# Power_DDRTermination.net
KiCad netlist of a schematic drawn in Altium Designer
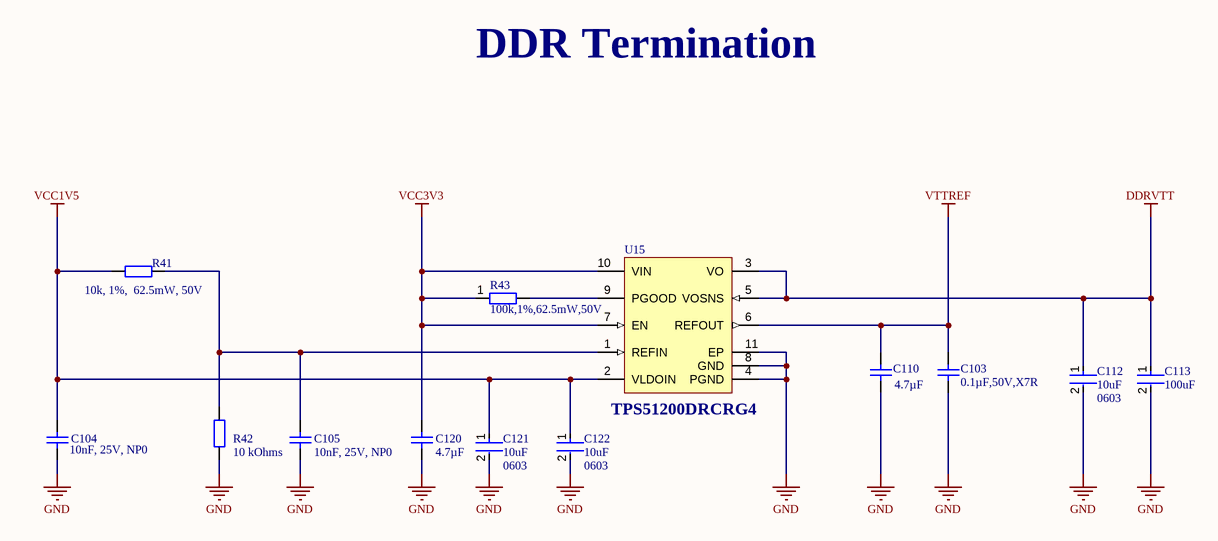
[diagram p0: Power_DDRTermination.SchDoc]

(export (version "E")
  (design (tool "Eeschema 10.0.6"))
  (components
    (comp (ref "C103")
      (value "0.1µF,50V,X7R")
      (footprint "CAP0402i")
      (description "0402, 0.1uF, 10%,  50V, X7R")
      (fields (field (name "PART NUMBER") "C1005X7R1H104K050BE") (field (name "VOLTAGE") "50V"))
      (libsource (lib "AmpherLib") (part "Cap_0.1uF_50V_X7R_0402"))
    )
    (comp (ref "C104")
      (value "10nF, 25V, NP0")
      (footprint "CAP0402i")
      (description "0402,10nF,5%,25V,NP0")
      (fields (field (name "PART NUMBER") "GRM1555C1E103JE01J") (field (name "MANUFACTURER") "Murata"))
      (libsource (lib "AmpherLib") (part "Cap_10nF_25V_NP0_0402"))
    )
    (comp (ref "C105")
      (value "10nF, 25V, NP0")
      (footprint "CAP0402i")
      (description "0402,10nF,5%,25V,NP0")
      (fields (field (name "PART NUMBER") "GRM1555C1E103JE01J") (field (name "MANUFACTURER") "Murata"))
      (libsource (lib "AmpherLib") (part "Cap_10nF_25V_NP0_0402"))
    )
    (comp (ref "C110")
      (value "4.7µF")
      (footprint "CAP0402i")
      (description "CAP CER 4.7UF 10V X5R 0402")
      (fields
        (field (name "TOLERANCE") "10%")
        (field (name "CAPACITANCE") "4.7µF")
        (field (name "PART NUMBER") "C1005X5R1A475K050BC")
      )
      (libsource (lib "AmpherLib") (part "Cap_4.7uF_10V_10%_0402"))
    )
    (comp (ref "C112")
      (value "GRM188R60J106ME47D")
      (footprint "FP-GRM188-0_1-e0_2_0_55-IPC_A")
      (description "Chip Multilayer Ceramic Capacitors for General Purpose, 0603, 10uF, X5R, 15%, 20%, 6.3V")
      (fields
        (field (name "CAPACITANCE") "10uF")
        (field (name "CASE/PACKAGE") "0603")
        (field (name "VOLTAGE") "6.3V")
        (field (name "TOLERANCE") "20%")
      )
      (libsource (lib "Altium Content Vault") (part "02cd4be3c70576c341d710602a673aa"))
    )
    (comp (ref "C113")
      (value "100uF")
      (footprint "FP-GRM32-0_3-MFG")
      (description "CAP CER 100UF 6.3V X5R 1210")
      (fields
        (field (name "OCTOPART") "https://octopart.com/grm32er60j107me20l-murata-197007")
        (field (name "3DS PART NUMBER") "220-00002")
      )
      (libsource (lib "Altium Content Vault") (part "11868f565c42a9108669ba33697ecf6"))
    )
    (comp (ref "C120")
      (value "4.7µF")
      (footprint "CAP0402i")
      (description "CAP CER 4.7UF 10V X5R 0402")
      (fields
        (field (name "TOLERANCE") "10%")
        (field (name "CAPACITANCE") "4.7µF")
        (field (name "PART NUMBER") "C1005X5R1A475K050BC")
      )
      (libsource (lib "AmpherLib") (part "Cap_4.7uF_10V_10%_0402"))
    )
    (comp (ref "C121")
      (value "GRM188R60J106ME47D")
      (footprint "FP-GRM188-0_1-e0_2_0_55-IPC_A")
      (description "Chip Multilayer Ceramic Capacitors for General Purpose, 0603, 10uF, X5R, 15%, 20%, 6.3V")
      (fields
        (field (name "CAPACITANCE") "10uF")
        (field (name "CASE/PACKAGE") "0603")
        (field (name "VOLTAGE") "6.3V")
        (field (name "TOLERANCE") "20%")
      )
      (libsource (lib "Altium Content Vault") (part "02cd4be3c70576c341d710602a673aa"))
    )
    (comp (ref "C122")
      (value "GRM188R60J106ME47D")
      (footprint "FP-GRM188-0_1-e0_2_0_55-IPC_A")
      (description "Chip Multilayer Ceramic Capacitors for General Purpose, 0603, 10uF, X5R, 15%, 20%, 6.3V")
      (fields
        (field (name "CAPACITANCE") "10uF")
        (field (name "CASE/PACKAGE") "0603")
        (field (name "VOLTAGE") "6.3V")
        (field (name "TOLERANCE") "20%")
      )
      (libsource (lib "Altium Content Vault") (part "02cd4be3c70576c341d710602a673aa"))
    )
    (comp (ref "R41")
      (value "10k, 1%,  62.5mW, 50V")
      (footprint "RES0402i")
      (description "0402, 10K 1%,  62.5mW, 50V")
      (fields (field (name "PART NUMBER") "CR0402-FX-1002GLF") (field (name "VOLTAGE") "50V"))
      (libsource (lib "") (part "Res_10k_1%_0402_1"))
    )
    (comp (ref "R42")
      (value "10 kOhms")
      (footprint "RES0402i")
      (description "0402, 10K 1%,  62.5mW, 50V")
      (fields
        (field (name "PART NUMBER") "CR0402-FX-1002GLF")
        (field (name "VOLTAGE") "50V")
        (field (name "RESISTANCE") "10 kOhms")
      )
      (libsource (lib "AmpherLib") (part "Res_10k_1%_0402"))
    )
    (comp (ref "R43")
      (value "100k,1%,62.5mW,50V")
      (footprint "RES0402i")
      (description "0402, 100k, 1%, 62.5mW, 50V")
      (fields (field (name "PART NUMBER") "CR0402-FX-1003GLF") (field (name "VOLTAGE") "50 V"))
      (libsource (lib "AmpherLib") (part "Res_100K_1%_0402"))
    )
    (comp (ref "U15")
      (value "TPS51200DRCRG4")
      (footprint "TI-DRC10-2400X1650TP_V")
      (fields (field (name "MANUFACTURER") "Texas Instruments"))
      (libsource (lib "Altium Content Vault") (part "TI-TPS51200DRC10-2400X1650TP"))
    )
  )
  (nets
    (net (code "1") (name "DDRVTT") (class "Default")
      (node (ref "C112") (pin "1") (pinfunction "1_1") (pintype "passive"))
      (node (ref "C113") (pin "1") (pinfunction "1_1") (pintype "passive"))
      (node (ref "U15") (pin "3") (pinfunction "VO_3") (pintype "power_in"))
      (node (ref "U15") (pin "5") (pinfunction "VOSNS_5") (pintype "input"))
    )
    (net (code "2") (name "GND") (class "Default")
      (node (ref "C103") (pin "1") (pinfunction "1_1") (pintype "passive"))
      (node (ref "C104") (pin "1") (pinfunction "1_1") (pintype "passive"))
      (node (ref "C105") (pin "1") (pinfunction "1_1") (pintype "passive"))
      (node (ref "C110") (pin "1") (pinfunction "1_1") (pintype "passive"))
      (node (ref "C112") (pin "2") (pinfunction "2_2") (pintype "passive"))
      (node (ref "C113") (pin "2") (pinfunction "2_2") (pintype "passive"))
      (node (ref "C120") (pin "1") (pinfunction "1_1") (pintype "passive"))
      (node (ref "C121") (pin "2") (pinfunction "2_2") (pintype "passive"))
      (node (ref "C122") (pin "2") (pinfunction "2_2") (pintype "passive"))
      (node (ref "R42") (pin "1") (pinfunction "1_1") (pintype "passive"))
      (node (ref "U15") (pin "11") (pinfunction "EP_11") (pintype "power_in"))
      (node (ref "U15") (pin "4") (pinfunction "PGND_4") (pintype "power_in"))
      (node (ref "U15") (pin "8") (pinfunction "GND_8") (pintype "power_in"))
    )
    (net (code "3") (name "Net-(U15-PGOOD)") (class "Default")
      (node (ref "R43") (pin "2") (pinfunction "2_2") (pintype "passive"))
      (node (ref "U15") (pin "9") (pinfunction "PGOOD_9") (pintype "open_collector"))
    )
    (net (code "4") (name "Net-(U15-REFIN)") (class "Default")
      (node (ref "C105") (pin "2") (pinfunction "2_2") (pintype "passive"))
      (node (ref "R41") (pin "2") (pinfunction "2_2") (pintype "passive"))
      (node (ref "R42") (pin "2") (pinfunction "2_2") (pintype "passive"))
      (node (ref "U15") (pin "1") (pinfunction "REFIN_1") (pintype "input"))
    )
    (net (code "5") (name "VCC1V5") (class "Default")
      (node (ref "C104") (pin "2") (pinfunction "2_2") (pintype "passive"))
      (node (ref "C121") (pin "1") (pinfunction "1_1") (pintype "passive"))
      (node (ref "C122") (pin "1") (pinfunction "1_1") (pintype "passive"))
      (node (ref "R41") (pin "1") (pinfunction "1_1") (pintype "passive"))
      (node (ref "U15") (pin "2") (pinfunction "VLDOIN_2") (pintype "power_in"))
    )
    (net (code "6") (name "VCC3V3") (class "Default")
      (node (ref "C120") (pin "2") (pinfunction "2_2") (pintype "passive"))
      (node (ref "R43") (pin "1") (pinfunction "1_1") (pintype "passive"))
      (node (ref "U15") (pin "10") (pinfunction "VIN_10") (pintype "power_in"))
      (node (ref "U15") (pin "7") (pinfunction "EN_7") (pintype "input"))
    )
    (net (code "7") (name "VTTREF") (class "Default")
      (node (ref "C103") (pin "2") (pinfunction "2_2") (pintype "passive"))
      (node (ref "C110") (pin "2") (pinfunction "2_2") (pintype "passive"))
      (node (ref "U15") (pin "6") (pinfunction "REFOUT_6") (pintype "output"))
    )
  )
)
